# aaduino-v2.net
KiCad netlist of a schematic drawn in EAGLE
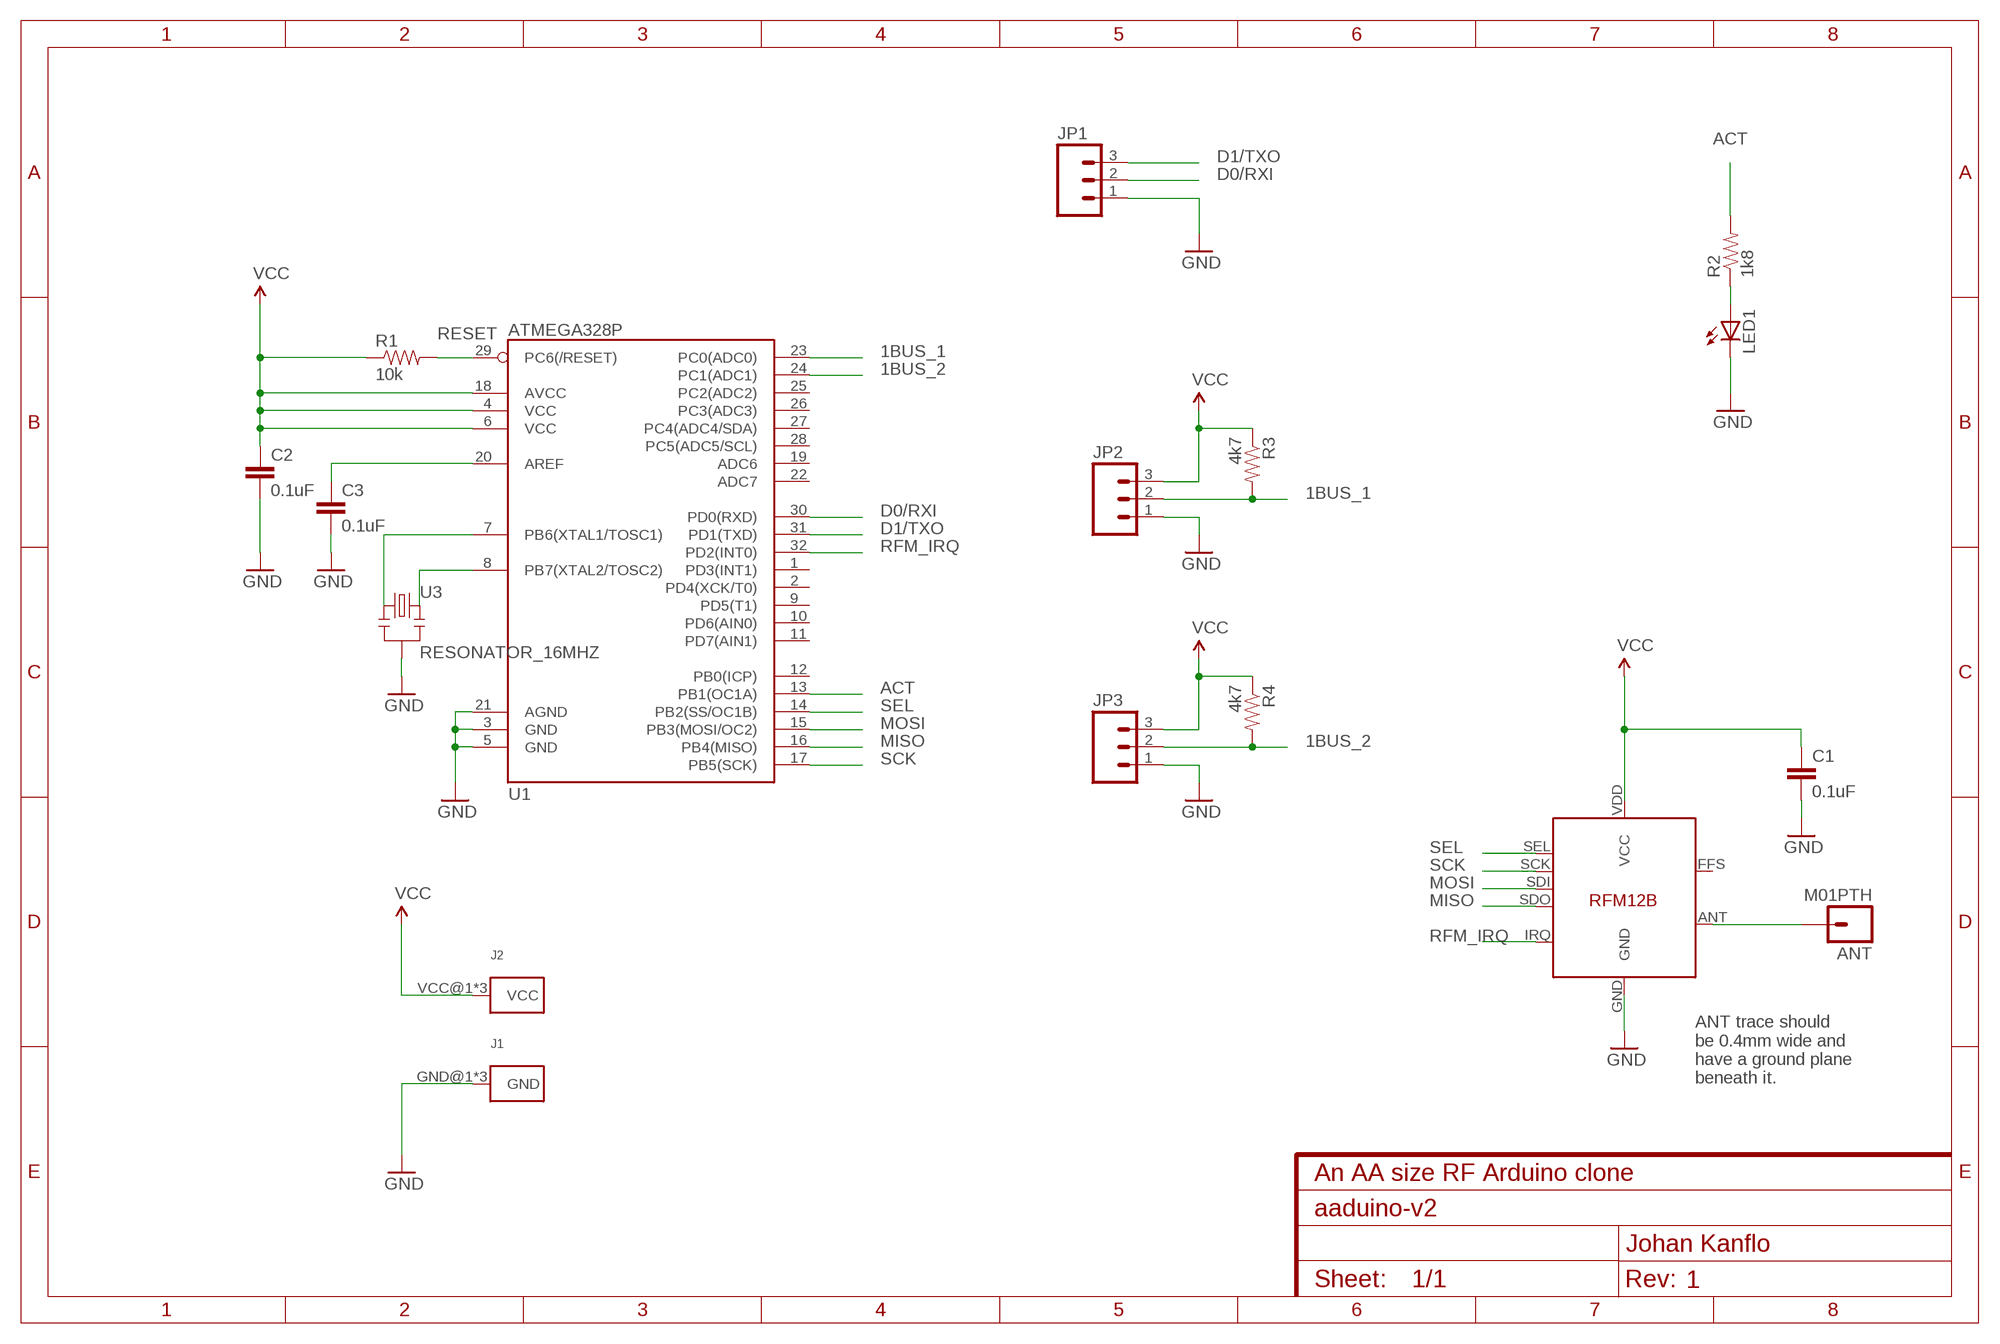
[diagram p0: schematic, sheet 1]

(export (version "E")
  (design (tool "Eeschema 10.0.6"))
  (components
    (comp (ref "ANT")
      (value "M01PTH")
      (footprint "eagle-import:1X01")
      (libsource (lib "eagle-import") (part "M01PTH"))
    )
    (comp (ref "C1")
      (value "0.1uF")
      (footprint "eagle-import:0603-CAP")
      (libsource (lib "eagle-import") (part "0.1UF-25V(+80/-20%)(0603)"))
    )
    (comp (ref "C2")
      (value "0.1uF")
      (footprint "eagle-import:0603-CAP")
      (libsource (lib "eagle-import") (part "0.1UF-25V(+80/-20%)(0603)"))
    )
    (comp (ref "C3")
      (value "0.1uF")
      (footprint "eagle-import:0603-CAP")
      (libsource (lib "eagle-import") (part "0.1UF-25V(+80/-20%)(0603)"))
    )
    (comp (ref "J1")
      (value "KEYSTONE-629")
      (footprint "eagle-import:KEYSTONE_AA_AAA_BATTERY_TERMINAL-629")
      (libsource (lib "eagle-import") (part "KEYSTONE-629"))
    )
    (comp (ref "J2")
      (value "KEYSTONE-637")
      (footprint "eagle-import:KEYSTONE_AA_AAA_BATTERY_TERMINAL-637")
      (libsource (lib "eagle-import") (part "KEYSTONE-637"))
    )
    (comp (ref "JP1")
      (value "M03PTH")
      (footprint "eagle-import:1X03")
      (libsource (lib "eagle-import") (part "M03PTH"))
    )
    (comp (ref "JP2")
      (value "M03PTH")
      (footprint "eagle-import:1X03")
      (libsource (lib "eagle-import") (part "M03PTH"))
    )
    (comp (ref "JP3")
      (value "M03PTH")
      (footprint "eagle-import:1X03")
      (libsource (lib "eagle-import") (part "M03PTH"))
    )
    (comp (ref "LED1")
      (value "LED0603")
      (footprint "eagle-import:LED-0603")
      (libsource (lib "eagle-import") (part "LED0603"))
    )
    (comp (ref "R1")
      (value "10k")
      (footprint "eagle-import:0603-RES")
      (libsource (lib "eagle-import") (part "RESISTOR0603-RES"))
    )
    (comp (ref "R2")
      (value "1k8")
      (footprint "eagle-import:0603-RES")
      (libsource (lib "eagle-import") (part "RESISTOR0603-RES"))
    )
    (comp (ref "R3")
      (value "4k7")
      (footprint "eagle-import:0603-RES")
      (libsource (lib "eagle-import") (part "RESISTOR0603-RES"))
    )
    (comp (ref "R4")
      (value "4k7")
      (footprint "eagle-import:0603-RES")
      (libsource (lib "eagle-import") (part "RESISTOR0603-RES"))
    )
    (comp (ref "U1")
      (value "ATMEGA328P")
      (footprint "eagle-import:TQFP32-08")
      (libsource (lib "eagle-import") (part "ATMEGA328_SMT"))
    )
    (comp (ref "U2")
      (value "RFM12B")
      (footprint "eagle-import:RFM12B")
      (libsource (lib "eagle-import") (part "RFM12B"))
    )
    (comp (ref "U3")
      (value "RESONATOR_16MHZ")
      (footprint "eagle-import:RESONATOR_SMD")
      (libsource (lib "eagle-import") (part "RESONATOR_16MHZ"))
    )
  )
  (nets
    (net (code "1") (name "/1BUS_1") (class "Default")
      (node (ref "JP2") (pin "2") (pinfunction "2_2") (pintype "passive"))
      (node (ref "R3") (pin "2") (pinfunction "2_2") (pintype "passive"))
      (node (ref "U1") (pin "23") (pinfunction "PC0(ADC0)_23") (pintype "bidirectional"))
    )
    (net (code "2") (name "/1BUS_2") (class "Default")
      (node (ref "JP3") (pin "2") (pinfunction "2_2") (pintype "passive"))
      (node (ref "R4") (pin "2") (pinfunction "2_2") (pintype "passive"))
      (node (ref "U1") (pin "24") (pinfunction "PC1(ADC1)_24") (pintype "bidirectional"))
    )
    (net (code "3") (name "/ACT") (class "Default")
      (node (ref "R2") (pin "2") (pinfunction "2_2") (pintype "passive"))
      (node (ref "U1") (pin "13") (pinfunction "PB1(OC1A)_13") (pintype "bidirectional"))
    )
    (net (code "4") (name "/D0{slash}RXI") (class "Default")
      (node (ref "JP1") (pin "2") (pinfunction "2_2") (pintype "passive"))
      (node (ref "U1") (pin "30") (pinfunction "PD0(RXD)_30") (pintype "bidirectional"))
    )
    (net (code "5") (name "/D1{slash}TXO") (class "Default")
      (node (ref "JP1") (pin "3") (pinfunction "3_3") (pintype "passive"))
      (node (ref "U1") (pin "31") (pinfunction "PD1(TXD)_31") (pintype "bidirectional"))
    )
    (net (code "6") (name "/MISO") (class "Default")
      (node (ref "U1") (pin "16") (pinfunction "PB4(MISO)_16") (pintype "bidirectional"))
      (node (ref "U2") (pin "SDO") (pinfunction "SDO_SDO") (pintype "output"))
    )
    (net (code "7") (name "/MOSI") (class "Default")
      (node (ref "U1") (pin "15") (pinfunction "PB3(MOSI/OC2)_15") (pintype "bidirectional"))
      (node (ref "U2") (pin "SDI") (pinfunction "SDI_SDI") (pintype "input"))
    )
    (net (code "8") (name "/RESET") (class "Default")
      (node (ref "R1") (pin "2") (pinfunction "2_2") (pintype "passive"))
      (node (ref "U1") (pin "29") (pinfunction "PC6(/RESET)_29") (pintype "bidirectional"))
    )
    (net (code "9") (name "/RFM_IRQ") (class "Default")
      (node (ref "U1") (pin "32") (pinfunction "PD2(INT0)_32") (pintype "bidirectional"))
      (node (ref "U2") (pin "IRQ") (pinfunction "IRQ_IRQ") (pintype "open_collector"))
    )
    (net (code "10") (name "/SCK") (class "Default")
      (node (ref "U1") (pin "17") (pinfunction "PB5(SCK)_17") (pintype "bidirectional"))
      (node (ref "U2") (pin "SCK") (pinfunction "SCK_SCK") (pintype "input"))
    )
    (net (code "11") (name "/SEL") (class "Default")
      (node (ref "U1") (pin "14") (pinfunction "PB2(SS/OC1B)_14") (pintype "bidirectional"))
      (node (ref "U2") (pin "SEL") (pinfunction "SEL_SEL") (pintype "input"))
    )
    (net (code "12") (name "GND") (class "Default")
      (node (ref "C1") (pin "2") (pinfunction "2_2") (pintype "passive"))
      (node (ref "C2") (pin "2") (pinfunction "2_2") (pintype "passive"))
      (node (ref "C3") (pin "2") (pinfunction "2_2") (pintype "passive"))
      (node (ref "J1") (pin "GND@1") (pinfunction "GND_GND@1") (pintype "power_in"))
      (node (ref "J1") (pin "GND@2") (pinfunction "GND_GND@2") (pintype "power_in"))
      (node (ref "J1") (pin "GND@3") (pinfunction "GND_GND@3") (pintype "power_in"))
      (node (ref "JP1") (pin "1") (pinfunction "1_1") (pintype "passive"))
      (node (ref "JP2") (pin "1") (pinfunction "1_1") (pintype "passive"))
      (node (ref "JP3") (pin "1") (pinfunction "1_1") (pintype "passive"))
      (node (ref "LED1") (pin "C") (pinfunction "C_C") (pintype "passive"))
      (node (ref "U1") (pin "21") (pinfunction "AGND_21") (pintype "bidirectional"))
      (node (ref "U1") (pin "3") (pinfunction "GND_3") (pintype "bidirectional"))
      (node (ref "U1") (pin "5") (pinfunction "GND_5") (pintype "bidirectional"))
      (node (ref "U2") (pin "GND") (pinfunction "GND_GND") (pintype "power_in"))
      (node (ref "U3") (pin "2") (pinfunction "2_2") (pintype "passive"))
    )
    (net (code "13") (name "Net-(ANT-Pad1)") (class "Default")
      (node (ref "ANT") (pin "1") (pinfunction "1_1") (pintype "passive"))
      (node (ref "U2") (pin "ANT") (pinfunction "ANT_ANT") (pintype "passive"))
    )
    (net (code "14") (name "Net-(LED1-PadA)") (class "Default")
      (node (ref "LED1") (pin "A") (pinfunction "A_A") (pintype "passive"))
      (node (ref "R2") (pin "1") (pinfunction "1_1") (pintype "passive"))
    )
    (net (code "15") (name "Net-(U1-AREF)") (class "Default")
      (node (ref "C3") (pin "1") (pinfunction "1_1") (pintype "passive"))
      (node (ref "U1") (pin "20") (pinfunction "AREF_20") (pintype "bidirectional"))
    )
    (net (code "16") (name "Net-(U1-PB6(XTAL1{slash}TOSC1))") (class "Default")
      (node (ref "U1") (pin "7") (pinfunction "PB6(XTAL1/TOSC1)_7") (pintype "bidirectional"))
      (node (ref "U3") (pin "1") (pinfunction "1_1") (pintype "passive"))
    )
    (net (code "17") (name "Net-(U1-PB7(XTAL2{slash}TOSC2))") (class "Default")
      (node (ref "U1") (pin "8") (pinfunction "PB7(XTAL2/TOSC2)_8") (pintype "bidirectional"))
      (node (ref "U3") (pin "3") (pinfunction "3_3") (pintype "passive"))
    )
    (net (code "18") (name "VCC") (class "Default")
      (node (ref "C1") (pin "1") (pinfunction "1_1") (pintype "passive"))
      (node (ref "C2") (pin "1") (pinfunction "1_1") (pintype "passive"))
      (node (ref "J2") (pin "VCC@1") (pinfunction "VCC_VCC@1") (pintype "power_in"))
      (node (ref "J2") (pin "VCC@2") (pinfunction "VCC_VCC@2") (pintype "power_in"))
      (node (ref "J2") (pin "VCC@3") (pinfunction "VCC_VCC@3") (pintype "power_in"))
      (node (ref "JP2") (pin "3") (pinfunction "3_3") (pintype "passive"))
      (node (ref "JP3") (pin "3") (pinfunction "3_3") (pintype "passive"))
      (node (ref "R1") (pin "1") (pinfunction "1_1") (pintype "passive"))
      (node (ref "R3") (pin "1") (pinfunction "1_1") (pintype "passive"))
      (node (ref "R4") (pin "1") (pinfunction "1_1") (pintype "passive"))
      (node (ref "U1") (pin "18") (pinfunction "AVCC_18") (pintype "bidirectional"))
      (node (ref "U1") (pin "4") (pinfunction "VCC_4") (pintype "bidirectional"))
      (node (ref "U1") (pin "6") (pinfunction "VCC_6") (pintype "bidirectional"))
      (node (ref "U2") (pin "VDD") (pinfunction "VCC_VDD") (pintype "power_in"))
    )
    (net (code "19") (name "unconnected-(U1-ADC6-Pad19)") (class "Default")
      (node (ref "U1") (pin "19") (pinfunction "ADC6_19") (pintype "bidirectional"))
    )
    (net (code "20") (name "unconnected-(U1-ADC7-Pad22)") (class "Default")
      (node (ref "U1") (pin "22") (pinfunction "ADC7_22") (pintype "bidirectional"))
    )
    (net (code "21") (name "unconnected-(U1-PB0(ICP)-Pad12)") (class "Default")
      (node (ref "U1") (pin "12") (pinfunction "PB0(ICP)_12") (pintype "bidirectional"))
    )
    (net (code "22") (name "unconnected-(U1-PC2(ADC2)-Pad25)") (class "Default")
      (node (ref "U1") (pin "25") (pinfunction "PC2(ADC2)_25") (pintype "bidirectional"))
    )
    (net (code "23") (name "unconnected-(U1-PC3(ADC3)-Pad26)") (class "Default")
      (node (ref "U1") (pin "26") (pinfunction "PC3(ADC3)_26") (pintype "bidirectional"))
    )
    (net (code "24") (name "unconnected-(U1-PC4(ADC4{slash}SDA)-Pad27)") (class "Default")
      (node (ref "U1") (pin "27") (pinfunction "PC4(ADC4/SDA)_27") (pintype "bidirectional"))
    )
    (net (code "25") (name "unconnected-(U1-PC5(ADC5{slash}SCL)-Pad28)") (class "Default")
      (node (ref "U1") (pin "28") (pinfunction "PC5(ADC5/SCL)_28") (pintype "bidirectional"))
    )
    (net (code "26") (name "unconnected-(U1-PD3(INT1)-Pad1)") (class "Default")
      (node (ref "U1") (pin "1") (pinfunction "PD3(INT1)_1") (pintype "bidirectional"))
    )
    (net (code "27") (name "unconnected-(U1-PD4(XCK{slash}T0)-Pad2)") (class "Default")
      (node (ref "U1") (pin "2") (pinfunction "PD4(XCK/T0)_2") (pintype "bidirectional"))
    )
    (net (code "28") (name "unconnected-(U1-PD5(T1)-Pad9)") (class "Default")
      (node (ref "U1") (pin "9") (pinfunction "PD5(T1)_9") (pintype "bidirectional"))
    )
    (net (code "29") (name "unconnected-(U1-PD6(AIN0)-Pad10)") (class "Default")
      (node (ref "U1") (pin "10") (pinfunction "PD6(AIN0)_10") (pintype "bidirectional"))
    )
    (net (code "30") (name "unconnected-(U1-PD7(AIN1)-Pad11)") (class "Default")
      (node (ref "U1") (pin "11") (pinfunction "PD7(AIN1)_11") (pintype "bidirectional"))
    )
    (net (code "31") (name "unconnected-(U2-PadFFS)") (class "Default")
      (node (ref "U2") (pin "FFS") (pinfunction "FFS_FFS") (pintype "bidirectional"))
    )
  )
)
